# EMS4ChibaRobo.net
KiCad netlist of a schematic drawn in EAGLE
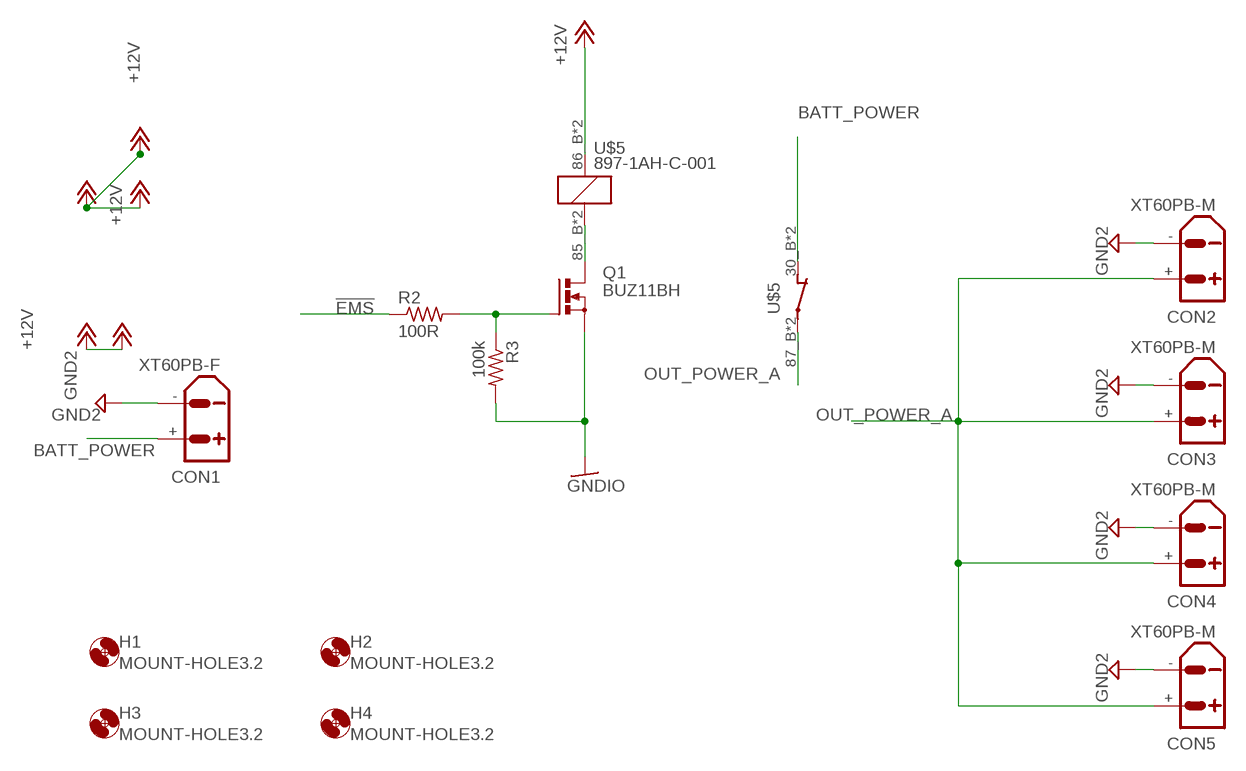
[diagram p0: schematic, sheet 1]
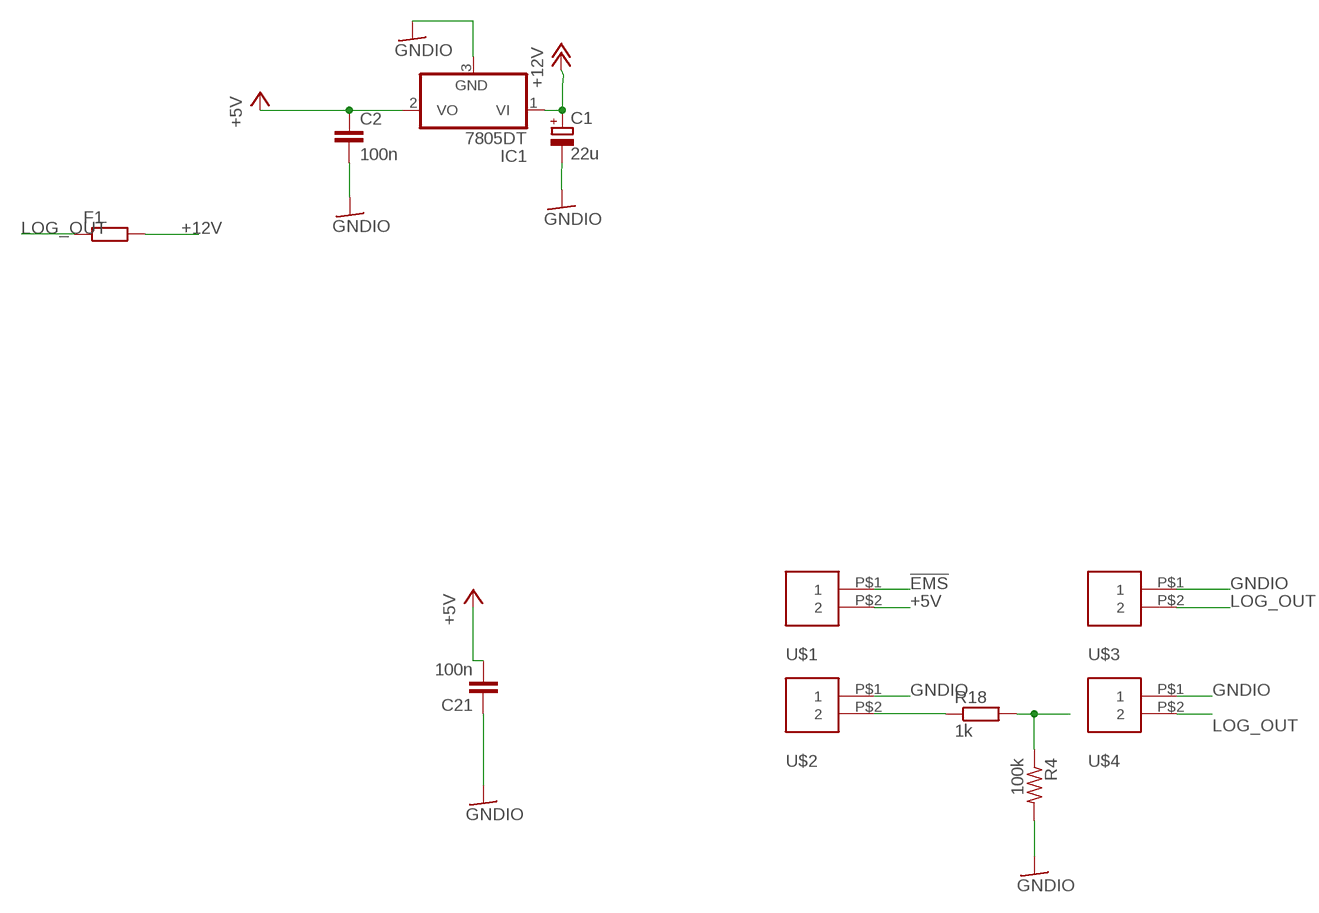
[diagram p1: schematic, sheet 2]

(export (version "E")
  (design (tool "Eeschema 10.0.6"))
  (components
    (comp (ref "CON1")
      (value "XT60PB-F")
      (footprint "eagle-import:XT60PB-F")
      (libsource (lib "eagle-import") (part "XT60PB-F"))
    )
    (comp (ref "CON2")
      (value "XT60PB-M")
      (footprint "eagle-import:XT60PB-M")
      (libsource (lib "eagle-import") (part "XT60PB-M"))
    )
    (comp (ref "CON3")
      (value "XT60PB-M")
      (footprint "eagle-import:XT60PB-M")
      (libsource (lib "eagle-import") (part "XT60PB-M"))
    )
    (comp (ref "CON4")
      (value "XT60PB-M")
      (footprint "eagle-import:XT60PB-M")
      (libsource (lib "eagle-import") (part "XT60PB-M"))
    )
    (comp (ref "CON5")
      (value "XT60PB-M")
      (footprint "eagle-import:XT60PB-M")
      (libsource (lib "eagle-import") (part "XT60PB-M"))
    )
    (comp (ref "H1")
      (value "MOUNT-HOLE3.2")
      (footprint "eagle-import:3,2")
      (libsource (lib "eagle-import") (part "MOUNT-HOLE3.2"))
    )
    (comp (ref "H2")
      (value "MOUNT-HOLE3.2")
      (footprint "eagle-import:3,2")
      (libsource (lib "eagle-import") (part "MOUNT-HOLE3.2"))
    )
    (comp (ref "H3")
      (value "MOUNT-HOLE3.2")
      (footprint "eagle-import:3,2")
      (libsource (lib "eagle-import") (part "MOUNT-HOLE3.2"))
    )
    (comp (ref "H4")
      (value "MOUNT-HOLE3.2")
      (footprint "eagle-import:3,2")
      (libsource (lib "eagle-import") (part "MOUNT-HOLE3.2"))
    )
    (comp (ref "Q1")
      (value "BUZ11BH")
      (footprint "eagle-import:TO220BH")
      (libsource (lib "eagle-import") (part "BUZ11BH"))
    )
    (comp (ref "R2")
      (value "100R")
      (footprint "eagle-import:R0603")
      (libsource (lib "eagle-import") (part "R-US_R0603"))
    )
    (comp (ref "R3")
      (value "100k")
      (footprint "eagle-import:R0603")
      (libsource (lib "eagle-import") (part "R-US_R0603"))
    )
    (comp (ref "U$5")
      (value "897-1AH-C-001")
      (footprint "eagle-import:897-1AH-C-001")
      (libsource (lib "eagle-import") (part "897-1AH-C-001"))
    )
    (comp (ref "C1")
      (value "22u")
      (footprint "eagle-import:E2,5-5")
      (libsource (lib "eagle-import") (part "CPOL-EUE2.5-5"))
    )
    (comp (ref "C2")
      (value "100n")
      (footprint "eagle-import:C0603")
      (libsource (lib "eagle-import") (part "rcl_334_C-EUC0603"))
    )
    (comp (ref "C21")
      (value "100n")
      (footprint "eagle-import:C0603")
      (libsource (lib "eagle-import") (part "C-EUC0603"))
    )
    (comp (ref "F1")
      (value "R-EU_R1206")
      (footprint "eagle-import:R1206")
      (libsource (lib "eagle-import") (part "R-EU_R1206"))
    )
    (comp (ref "IC1")
      (value "7805DT")
      (footprint "eagle-import:TO252")
      (libsource (lib "eagle-import") (part "78DT05"))
    )
    (comp (ref "R4")
      (value "100k")
      (footprint "eagle-import:R0603")
      (libsource (lib "eagle-import") (part "R-US_R0603"))
    )
    (comp (ref "R18")
      (value "1k")
      (footprint "eagle-import:R0603")
      (libsource (lib "eagle-import") (part "R-EU_R0603"))
    )
    (comp (ref "U$1")
      (value "XH-2-STRAIGHT")
      (footprint "eagle-import:CON-XH-2-STRAIGHT")
      (libsource (lib "eagle-import") (part "XH-2-STRAIGHT"))
    )
    (comp (ref "U$2")
      (value "XH-2-STRAIGHT")
      (footprint "eagle-import:CON-XH-2-STRAIGHT")
      (libsource (lib "eagle-import") (part "XH-2-STRAIGHT"))
    )
    (comp (ref "U$3")
      (value "XH-2-STRAIGHT")
      (footprint "eagle-import:CON-XH-2-STRAIGHT")
      (libsource (lib "eagle-import") (part "XH-2-STRAIGHT"))
    )
    (comp (ref "U$4")
      (value "XH-2-STRAIGHT")
      (footprint "eagle-import:CON-XH-2-STRAIGHT")
      (libsource (lib "eagle-import") (part "XH-2-STRAIGHT"))
    )
  )
  (nets
    (net (code "1") (name "+5V") (class "Default")
      (node (ref "C2") (pin "1") (pinfunction "1_1") (pintype "passive"))
      (node (ref "C21") (pin "2") (pinfunction "2_2") (pintype "passive"))
      (node (ref "IC1") (pin "2") (pinfunction "VO_2") (pintype "passive"))
      (node (ref "U$1") (pin "P$2") (pinfunction "2_P$2") (pintype "bidirectional"))
    )
    (net (code "2") (name "+12V") (class "Default")
      (node (ref "C1") (pin "+") (pinfunction "+_+") (pintype "passive"))
      (node (ref "F1") (pin "2") (pinfunction "2_2") (pintype "passive"))
      (node (ref "IC1") (pin "1") (pinfunction "VI_1") (pintype "input"))
      (node (ref "U$5") (pin "86_B") (pinfunction "1_86_B") (pintype "passive"))
      (node (ref "U$5") (pin "86_T") (pinfunction "1_86_T") (pintype "passive"))
    )
    (net (code "3") (name "BATT_POWER") (class "Default")
      (node (ref "CON1") (pin "+") (pinfunction "+_+") (pintype "power_in"))
      (node (ref "U$5") (pin "30_B") (pinfunction "O_30_B") (pintype "passive"))
      (node (ref "U$5") (pin "30_T") (pinfunction "O_30_T") (pintype "passive"))
    )
    (net (code "4") (name "GND2") (class "Default")
      (node (ref "CON1") (pin "-") (pinfunction "-_-") (pintype "power_in"))
      (node (ref "CON2") (pin "-") (pinfunction "-_-") (pintype "power_in"))
      (node (ref "CON3") (pin "-") (pinfunction "-_-") (pintype "power_in"))
      (node (ref "CON4") (pin "-") (pinfunction "-_-") (pintype "power_in"))
      (node (ref "CON5") (pin "-") (pinfunction "-_-") (pintype "power_in"))
    )
    (net (code "5") (name "GNDIO") (class "Default")
      (node (ref "C1") (pin "-") (pinfunction "-_-") (pintype "passive"))
      (node (ref "C2") (pin "2") (pinfunction "2_2") (pintype "passive"))
      (node (ref "C21") (pin "1") (pinfunction "1_1") (pintype "passive"))
      (node (ref "IC1") (pin "3") (pinfunction "GND_3") (pintype "passive"))
      (node (ref "Q1") (pin "S") (pinfunction "S_S") (pintype "passive"))
      (node (ref "R3") (pin "2") (pinfunction "2_2") (pintype "passive"))
      (node (ref "R4") (pin "2") (pinfunction "2_2") (pintype "passive"))
      (node (ref "U$2") (pin "P$1") (pinfunction "1_P$1") (pintype "bidirectional"))
      (node (ref "U$3") (pin "P$1") (pinfunction "1_P$1") (pintype "bidirectional"))
      (node (ref "U$4") (pin "P$1") (pinfunction "1_P$1") (pintype "bidirectional"))
    )
    (net (code "6") (name "LOG_OUT") (class "Default")
      (node (ref "F1") (pin "1") (pinfunction "1_1") (pintype "passive"))
      (node (ref "U$3") (pin "P$2") (pinfunction "2_P$2") (pintype "bidirectional"))
      (node (ref "U$4") (pin "P$2") (pinfunction "2_P$2") (pintype "bidirectional"))
    )
    (net (code "7") (name "Net-(Q1-PadD)") (class "Default")
      (node (ref "Q1") (pin "D") (pinfunction "D_D") (pintype "passive"))
      (node (ref "U$5") (pin "85_B") (pinfunction "2_85_B") (pintype "passive"))
      (node (ref "U$5") (pin "85_T") (pinfunction "2_85_T") (pintype "passive"))
    )
    (net (code "8") (name "Net-(Q1-PadG)") (class "Default")
      (node (ref "Q1") (pin "G") (pinfunction "G_G") (pintype "passive"))
      (node (ref "R2") (pin "2") (pinfunction "2_2") (pintype "passive"))
      (node (ref "R3") (pin "1") (pinfunction "1_1") (pintype "passive"))
    )
    (net (code "9") (name "Net-(U$2-2)") (class "Default")
      (node (ref "R18") (pin "1") (pinfunction "1_1") (pintype "passive"))
      (node (ref "U$2") (pin "P$2") (pinfunction "2_P$2") (pintype "bidirectional"))
    )
    (net (code "10") (name "OUT_POWER_A") (class "Default")
      (node (ref "CON2") (pin "+") (pinfunction "+_+") (pintype "power_in"))
      (node (ref "CON3") (pin "+") (pinfunction "+_+") (pintype "power_in"))
      (node (ref "CON4") (pin "+") (pinfunction "+_+") (pintype "power_in"))
      (node (ref "CON5") (pin "+") (pinfunction "+_+") (pintype "power_in"))
      (node (ref "U$5") (pin "87_B") (pinfunction "P_87_B") (pintype "passive"))
      (node (ref "U$5") (pin "87_T") (pinfunction "P_87_T") (pintype "passive"))
    )
    (net (code "11") (name "~{EMS}") (class "Default")
      (node (ref "R18") (pin "2") (pinfunction "2_2") (pintype "passive"))
      (node (ref "R2") (pin "1") (pinfunction "1_1") (pintype "passive"))
      (node (ref "R4") (pin "1") (pinfunction "1_1") (pintype "passive"))
      (node (ref "U$1") (pin "P$1") (pinfunction "1_P$1") (pintype "bidirectional"))
    )
  )
)
